# Sheet1.net
KiCad netlist of a schematic drawn in Altium Designer
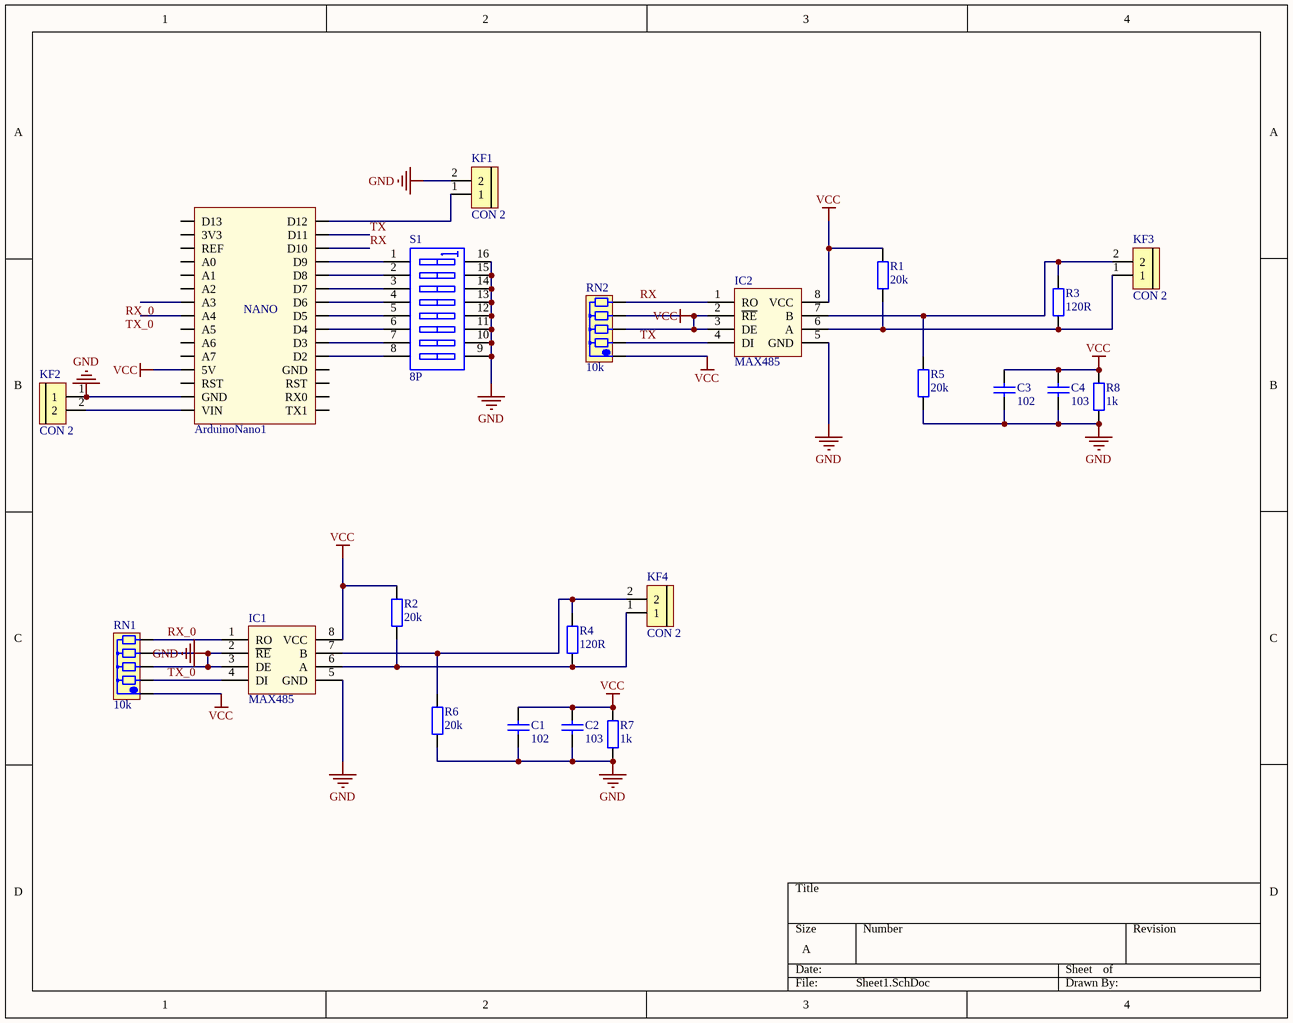
[diagram p0: Sheet1.SchDoc]

(export (version "E")
  (design (tool "Eeschema 10.0.6"))
  (components
    (comp (ref "ArduinoNano1")
      (value "Arduino Nano")
      (footprint "Arduino Nano")
      (description "Arduino NANO")
      (libsource (lib "LIBRARY") (part "Arduino Nano"))
    )
    (comp (ref "C1")
      (value "102")
      (footprint "tu gom")
      (description "Cắm")
      (libsource (lib "Altium_Lib_by_KhueNguyenCreator") (part "Tu gom 102 50V"))
    )
    (comp (ref "C2")
      (value "103")
      (footprint "tu gom")
      (description "Cắm")
      (libsource (lib "Altium_Lib_by_KhueNguyenCreator") (part "Tu gom 103 50V"))
    )
    (comp (ref "C3")
      (value "102")
      (footprint "tu gom")
      (description "Cắm")
      (libsource (lib "Altium_Lib_by_KhueNguyenCreator") (part "Tu gom 102 50V"))
    )
    (comp (ref "C4")
      (value "103")
      (footprint "tu gom")
      (description "Cắm")
      (libsource (lib "Altium_Lib_by_KhueNguyenCreator") (part "Tu gom 103 50V"))
    )
    (comp (ref "IC1")
      (value "MAX485")
      (footprint "DIP8/W0.3")
      (description "RS232 - RS485 (Same sn75176)")
      (libsource (lib "My Library") (part "MAX485"))
    )
    (comp (ref "IC2")
      (value "MAX485")
      (footprint "DIP8/W0.3")
      (description "RS232 - RS485 (Same sn75176)")
      (libsource (lib "My Library") (part "MAX485"))
    )
    (comp (ref "KF1")
      (value "CON 2")
      (footprint "Con 2 KF301 5.08")
      (description "Cắm")
      (libsource (lib "Altium_Lib_by_KhueNguyenCreator") (part "CON 2 KF301"))
    )
    (comp (ref "KF2")
      (value "CON 2")
      (footprint "Con 2 KF301 5.08")
      (description "Cắm")
      (libsource (lib "") (part "CON 2 KF301_1"))
    )
    (comp (ref "KF3")
      (value "CON 2")
      (footprint "Con 2 KF301 5.08")
      (description "Cắm")
      (libsource (lib "Altium_Lib_by_KhueNguyenCreator") (part "CON 2 KF301"))
    )
    (comp (ref "KF4")
      (value "CON 2")
      (footprint "Con 2 KF301 5.08")
      (description "Cắm")
      (libsource (lib "Altium_Lib_by_KhueNguyenCreator") (part "CON 2 KF301"))
    )
    (comp (ref "R1")
      (value "20k")
      (footprint "tro vach 1/4w")
      (description "Cắm")
      (libsource (lib "Altium_Lib_by_KhueNguyenCreator") (part "Tro Vach 1/4W 5% 20k"))
    )
    (comp (ref "R2")
      (value "20k")
      (footprint "tro vach 1/4w")
      (description "Cắm")
      (libsource (lib "Altium_Lib_by_KhueNguyenCreator") (part "Tro Vach 1/4W 5% 20k"))
    )
    (comp (ref "R3")
      (value "120R")
      (footprint "tro vach 1/4w")
      (description "Cắm")
      (libsource (lib "Altium_Lib_by_KhueNguyenCreator") (part "Tro Vach 1/4W 5% 120R"))
    )
    (comp (ref "R4")
      (value "120R")
      (footprint "tro vach 1/4w")
      (description "Cắm")
      (libsource (lib "Altium_Lib_by_KhueNguyenCreator") (part "Tro Vach 1/4W 5% 120R"))
    )
    (comp (ref "R5")
      (value "20k")
      (footprint "tro vach 1/4w")
      (description "Cắm")
      (libsource (lib "Altium_Lib_by_KhueNguyenCreator") (part "Tro Vach 1/4W 5% 20k"))
    )
    (comp (ref "R6")
      (value "20k")
      (footprint "tro vach 1/4w")
      (description "Cắm")
      (libsource (lib "Altium_Lib_by_KhueNguyenCreator") (part "Tro Vach 1/4W 5% 20k"))
    )
    (comp (ref "R7")
      (value "1k")
      (footprint "tro vach 1/4w")
      (description "Cắm")
      (libsource (lib "Altium_Lib_by_KhueNguyenCreator") (part "Tro Vach 1/4W 5% 1k"))
    )
    (comp (ref "R8")
      (value "1k")
      (footprint "tro vach 1/4w")
      (description "Cắm")
      (libsource (lib "Altium_Lib_by_KhueNguyenCreator") (part "Tro Vach 1/4W 5% 1k"))
    )
    (comp (ref "RN1")
      (value "10k")
      (footprint "RN4")
      (description "Resistor 4 (thanh)")
      (libsource (lib "Cty1") (part "RN4"))
    )
    (comp (ref "RN2")
      (value "10k")
      (footprint "RN4")
      (description "Resistor 4 (thanh)")
      (libsource (lib "Cty1") (part "RN4"))
    )
    (comp (ref "S1")
      (value "8P")
      (footprint "SW-DIP8")
      (description "Cắm")
      (libsource (lib "THU VIEN SCH") (part "Cong Tac Bits 8P"))
    )
  )
  (nets
    (net (code "1") (name "/RX") (class "Default")
      (node (ref "ArduinoNano1") (pin "D10") (pinfunction "D10_D10") (pintype "passive"))
      (node (ref "IC2") (pin "1") (pinfunction "RO_1") (pintype "passive"))
      (node (ref "RN2") (pin "5") (pinfunction "5_5") (pintype "passive"))
    )
    (net (code "2") (name "/RX_0") (class "Default")
      (node (ref "ArduinoNano1") (pin "A3") (pinfunction "A3_A3") (pintype "passive"))
      (node (ref "IC1") (pin "1") (pinfunction "RO_1") (pintype "passive"))
      (node (ref "RN1") (pin "5") (pinfunction "5_5") (pintype "passive"))
    )
    (net (code "3") (name "/TX") (class "Default")
      (node (ref "ArduinoNano1") (pin "D11") (pinfunction "D11_D11") (pintype "passive"))
      (node (ref "IC2") (pin "4") (pinfunction "DI_4") (pintype "passive"))
      (node (ref "RN2") (pin "2") (pinfunction "2_2") (pintype "passive"))
    )
    (net (code "4") (name "/TX_0") (class "Default")
      (node (ref "ArduinoNano1") (pin "A4") (pinfunction "A4_A4") (pintype "passive"))
      (node (ref "IC1") (pin "4") (pinfunction "DI_4") (pintype "passive"))
      (node (ref "RN1") (pin "2") (pinfunction "2_2") (pintype "passive"))
    )
    (net (code "5") (name "GND") (class "Default")
      (node (ref "ArduinoNano1") (pin "GND") (pinfunction "GND_GND") (pintype "passive"))
      (node (ref "C1") (pin "2") (pinfunction "2_2") (pintype "passive"))
      (node (ref "C2") (pin "2") (pinfunction "2_2") (pintype "passive"))
      (node (ref "C3") (pin "2") (pinfunction "2_2") (pintype "passive"))
      (node (ref "C4") (pin "2") (pinfunction "2_2") (pintype "passive"))
      (node (ref "IC1") (pin "2") (pinfunction "~{RE}_2") (pintype "passive"))
      (node (ref "IC1") (pin "3") (pinfunction "DE_3") (pintype "passive"))
      (node (ref "IC1") (pin "5") (pinfunction "GND_5") (pintype "passive"))
      (node (ref "IC2") (pin "5") (pinfunction "GND_5") (pintype "passive"))
      (node (ref "KF1") (pin "2") (pinfunction "2_2") (pintype "passive"))
      (node (ref "KF2") (pin "1") (pinfunction "1_1") (pintype "passive"))
      (node (ref "R5") (pin "1") (pinfunction "1_1") (pintype "passive"))
      (node (ref "R6") (pin "1") (pinfunction "1_1") (pintype "passive"))
      (node (ref "R7") (pin "1") (pinfunction "1_1") (pintype "passive"))
      (node (ref "R8") (pin "1") (pinfunction "1_1") (pintype "passive"))
      (node (ref "RN1") (pin "3") (pinfunction "3_3") (pintype "passive"))
      (node (ref "RN1") (pin "4") (pinfunction "4_4") (pintype "passive"))
      (node (ref "S1") (pin "10") (pinfunction "B7_10") (pintype "passive"))
      (node (ref "S1") (pin "11") (pinfunction "B6_11") (pintype "passive"))
      (node (ref "S1") (pin "12") (pinfunction "B5_12") (pintype "passive"))
      (node (ref "S1") (pin "13") (pinfunction "B4_13") (pintype "passive"))
      (node (ref "S1") (pin "14") (pinfunction "B3_14") (pintype "passive"))
      (node (ref "S1") (pin "15") (pinfunction "B2_15") (pintype "passive"))
      (node (ref "S1") (pin "16") (pinfunction "B1_16") (pintype "passive"))
      (node (ref "S1") (pin "9") (pinfunction "B8_9") (pintype "passive"))
    )
    (net (code "6") (name "Net-(ArduinoNano1-PadD12)") (class "Default")
      (node (ref "ArduinoNano1") (pin "D12") (pinfunction "D12_D12") (pintype "passive"))
      (node (ref "KF1") (pin "1") (pinfunction "1_1") (pintype "passive"))
    )
    (net (code "7") (name "Net-(ArduinoNano1-PadVIN)") (class "Default")
      (node (ref "ArduinoNano1") (pin "VIN") (pinfunction "VIN_VIN") (pintype "passive"))
      (node (ref "KF2") (pin "2") (pinfunction "2_2") (pintype "passive"))
    )
    (net (code "8") (name "Net-(IC1-A)") (class "Default")
      (node (ref "IC1") (pin "6") (pinfunction "A_6") (pintype "passive"))
      (node (ref "KF4") (pin "1") (pinfunction "1_1") (pintype "passive"))
      (node (ref "R2") (pin "1") (pinfunction "1_1") (pintype "passive"))
      (node (ref "R4") (pin "1") (pinfunction "1_1") (pintype "passive"))
    )
    (net (code "9") (name "Net-(IC1-B)") (class "Default")
      (node (ref "IC1") (pin "7") (pinfunction "B_7") (pintype "passive"))
      (node (ref "KF4") (pin "2") (pinfunction "2_2") (pintype "passive"))
      (node (ref "R4") (pin "2") (pinfunction "2_2") (pintype "passive"))
      (node (ref "R6") (pin "2") (pinfunction "2_2") (pintype "passive"))
    )
    (net (code "10") (name "Net-(IC2-A)") (class "Default")
      (node (ref "IC2") (pin "6") (pinfunction "A_6") (pintype "passive"))
      (node (ref "KF3") (pin "1") (pinfunction "1_1") (pintype "passive"))
      (node (ref "R1") (pin "1") (pinfunction "1_1") (pintype "passive"))
      (node (ref "R3") (pin "1") (pinfunction "1_1") (pintype "passive"))
    )
    (net (code "11") (name "Net-(IC2-B)") (class "Default")
      (node (ref "IC2") (pin "7") (pinfunction "B_7") (pintype "passive"))
      (node (ref "KF3") (pin "2") (pinfunction "2_2") (pintype "passive"))
      (node (ref "R3") (pin "2") (pinfunction "2_2") (pintype "passive"))
      (node (ref "R5") (pin "2") (pinfunction "2_2") (pintype "passive"))
    )
    (net (code "12") (name "Net-(S1-A1)") (class "Default")
      (node (ref "ArduinoNano1") (pin "D9") (pinfunction "D9_D9") (pintype "passive"))
      (node (ref "S1") (pin "1") (pinfunction "A1_1") (pintype "passive"))
    )
    (net (code "13") (name "Net-(S1-A2)") (class "Default")
      (node (ref "ArduinoNano1") (pin "D8") (pinfunction "D8_D8") (pintype "passive"))
      (node (ref "S1") (pin "2") (pinfunction "A2_2") (pintype "passive"))
    )
    (net (code "14") (name "Net-(S1-A3)") (class "Default")
      (node (ref "ArduinoNano1") (pin "D7") (pinfunction "D7_D7") (pintype "passive"))
      (node (ref "S1") (pin "3") (pinfunction "A3_3") (pintype "passive"))
    )
    (net (code "15") (name "Net-(S1-A4)") (class "Default")
      (node (ref "ArduinoNano1") (pin "D6") (pinfunction "D6_D6") (pintype "passive"))
      (node (ref "S1") (pin "4") (pinfunction "A4_4") (pintype "passive"))
    )
    (net (code "16") (name "Net-(S1-A5)") (class "Default")
      (node (ref "ArduinoNano1") (pin "D5") (pinfunction "D5_D5") (pintype "passive"))
      (node (ref "S1") (pin "5") (pinfunction "A5_5") (pintype "passive"))
    )
    (net (code "17") (name "Net-(S1-A6)") (class "Default")
      (node (ref "ArduinoNano1") (pin "D4") (pinfunction "D4_D4") (pintype "passive"))
      (node (ref "S1") (pin "6") (pinfunction "A6_6") (pintype "passive"))
    )
    (net (code "18") (name "Net-(S1-A7)") (class "Default")
      (node (ref "ArduinoNano1") (pin "D3") (pinfunction "D3_D3") (pintype "passive"))
      (node (ref "S1") (pin "7") (pinfunction "A7_7") (pintype "passive"))
    )
    (net (code "19") (name "Net-(S1-A8)") (class "Default")
      (node (ref "ArduinoNano1") (pin "D2") (pinfunction "D2_D2") (pintype "passive"))
      (node (ref "S1") (pin "8") (pinfunction "A8_8") (pintype "passive"))
    )
    (net (code "20") (name "VCC") (class "Default")
      (node (ref "ArduinoNano1") (pin "5V") (pinfunction "5V_5V") (pintype "passive"))
      (node (ref "C1") (pin "1") (pinfunction "1_1") (pintype "passive"))
      (node (ref "C2") (pin "1") (pinfunction "1_1") (pintype "passive"))
      (node (ref "C3") (pin "1") (pinfunction "1_1") (pintype "passive"))
      (node (ref "C4") (pin "1") (pinfunction "1_1") (pintype "passive"))
      (node (ref "IC1") (pin "8") (pinfunction "VCC_8") (pintype "passive"))
      (node (ref "IC2") (pin "2") (pinfunction "~{RE}_2") (pintype "passive"))
      (node (ref "IC2") (pin "3") (pinfunction "DE_3") (pintype "passive"))
      (node (ref "IC2") (pin "8") (pinfunction "VCC_8") (pintype "passive"))
      (node (ref "R1") (pin "2") (pinfunction "2_2") (pintype "passive"))
      (node (ref "R2") (pin "2") (pinfunction "2_2") (pintype "passive"))
      (node (ref "R7") (pin "2") (pinfunction "2_2") (pintype "passive"))
      (node (ref "R8") (pin "2") (pinfunction "2_2") (pintype "passive"))
      (node (ref "RN1") (pin "1") (pinfunction "1_1") (pintype "passive"))
      (node (ref "RN2") (pin "1") (pinfunction "1_1") (pintype "passive"))
      (node (ref "RN2") (pin "3") (pinfunction "3_3") (pintype "passive"))
      (node (ref "RN2") (pin "4") (pinfunction "4_4") (pintype "passive"))
    )
    (net (code "21") (name "unconnected-(ArduinoNano1-Pad3V3)") (class "Default")
      (node (ref "ArduinoNano1") (pin "3V3") (pinfunction "3V3_3V3") (pintype "passive"))
    )
    (net (code "22") (name "unconnected-(ArduinoNano1-PadA0)") (class "Default")
      (node (ref "ArduinoNano1") (pin "A0") (pinfunction "A0_A0") (pintype "passive"))
    )
    (net (code "23") (name "unconnected-(ArduinoNano1-PadA1)") (class "Default")
      (node (ref "ArduinoNano1") (pin "A1") (pinfunction "A1_A1") (pintype "passive"))
    )
    (net (code "24") (name "unconnected-(ArduinoNano1-PadA2)") (class "Default")
      (node (ref "ArduinoNano1") (pin "A2") (pinfunction "A2_A2") (pintype "passive"))
    )
    (net (code "25") (name "unconnected-(ArduinoNano1-PadA5)") (class "Default")
      (node (ref "ArduinoNano1") (pin "A5") (pinfunction "A5_A5") (pintype "passive"))
    )
    (net (code "26") (name "unconnected-(ArduinoNano1-PadA6)") (class "Default")
      (node (ref "ArduinoNano1") (pin "A6") (pinfunction "A6_A6") (pintype "passive"))
    )
    (net (code "27") (name "unconnected-(ArduinoNano1-PadA7)") (class "Default")
      (node (ref "ArduinoNano1") (pin "A7") (pinfunction "A7_A7") (pintype "passive"))
    )
    (net (code "28") (name "unconnected-(ArduinoNano1-PadD13)") (class "Default")
      (node (ref "ArduinoNano1") (pin "D13") (pinfunction "D13_D13") (pintype "passive"))
    )
    (net (code "29") (name "unconnected-(ArduinoNano1-PadGND)") (class "Default")
      (node (ref "ArduinoNano1") (pin "GND") (pinfunction "GND_GND") (pintype "passive"))
    )
    (net (code "30") (name "unconnected-(ArduinoNano1-PadREF)") (class "Default")
      (node (ref "ArduinoNano1") (pin "REF") (pinfunction "REF_REF") (pintype "passive"))
    )
    (net (code "31") (name "unconnected-(ArduinoNano1-PadRST)") (class "Default")
      (node (ref "ArduinoNano1") (pin "RST") (pinfunction "RST_RST") (pintype "passive"))
    )
    (net (code "32") (name "unconnected-(ArduinoNano1-PadRST)_1") (class "Default")
      (node (ref "ArduinoNano1") (pin "RST") (pinfunction "RST_RST") (pintype "passive"))
    )
    (net (code "33") (name "unconnected-(ArduinoNano1-PadRX0)") (class "Default")
      (node (ref "ArduinoNano1") (pin "RX0") (pinfunction "RX0_RX0") (pintype "passive"))
    )
    (net (code "34") (name "unconnected-(ArduinoNano1-PadTX1)") (class "Default")
      (node (ref "ArduinoNano1") (pin "TX1") (pinfunction "TX1_TX1") (pintype "passive"))
    )
  )
)
